# MS5803-2BA.net
KiCad netlist of a schematic drawn in EAGLE
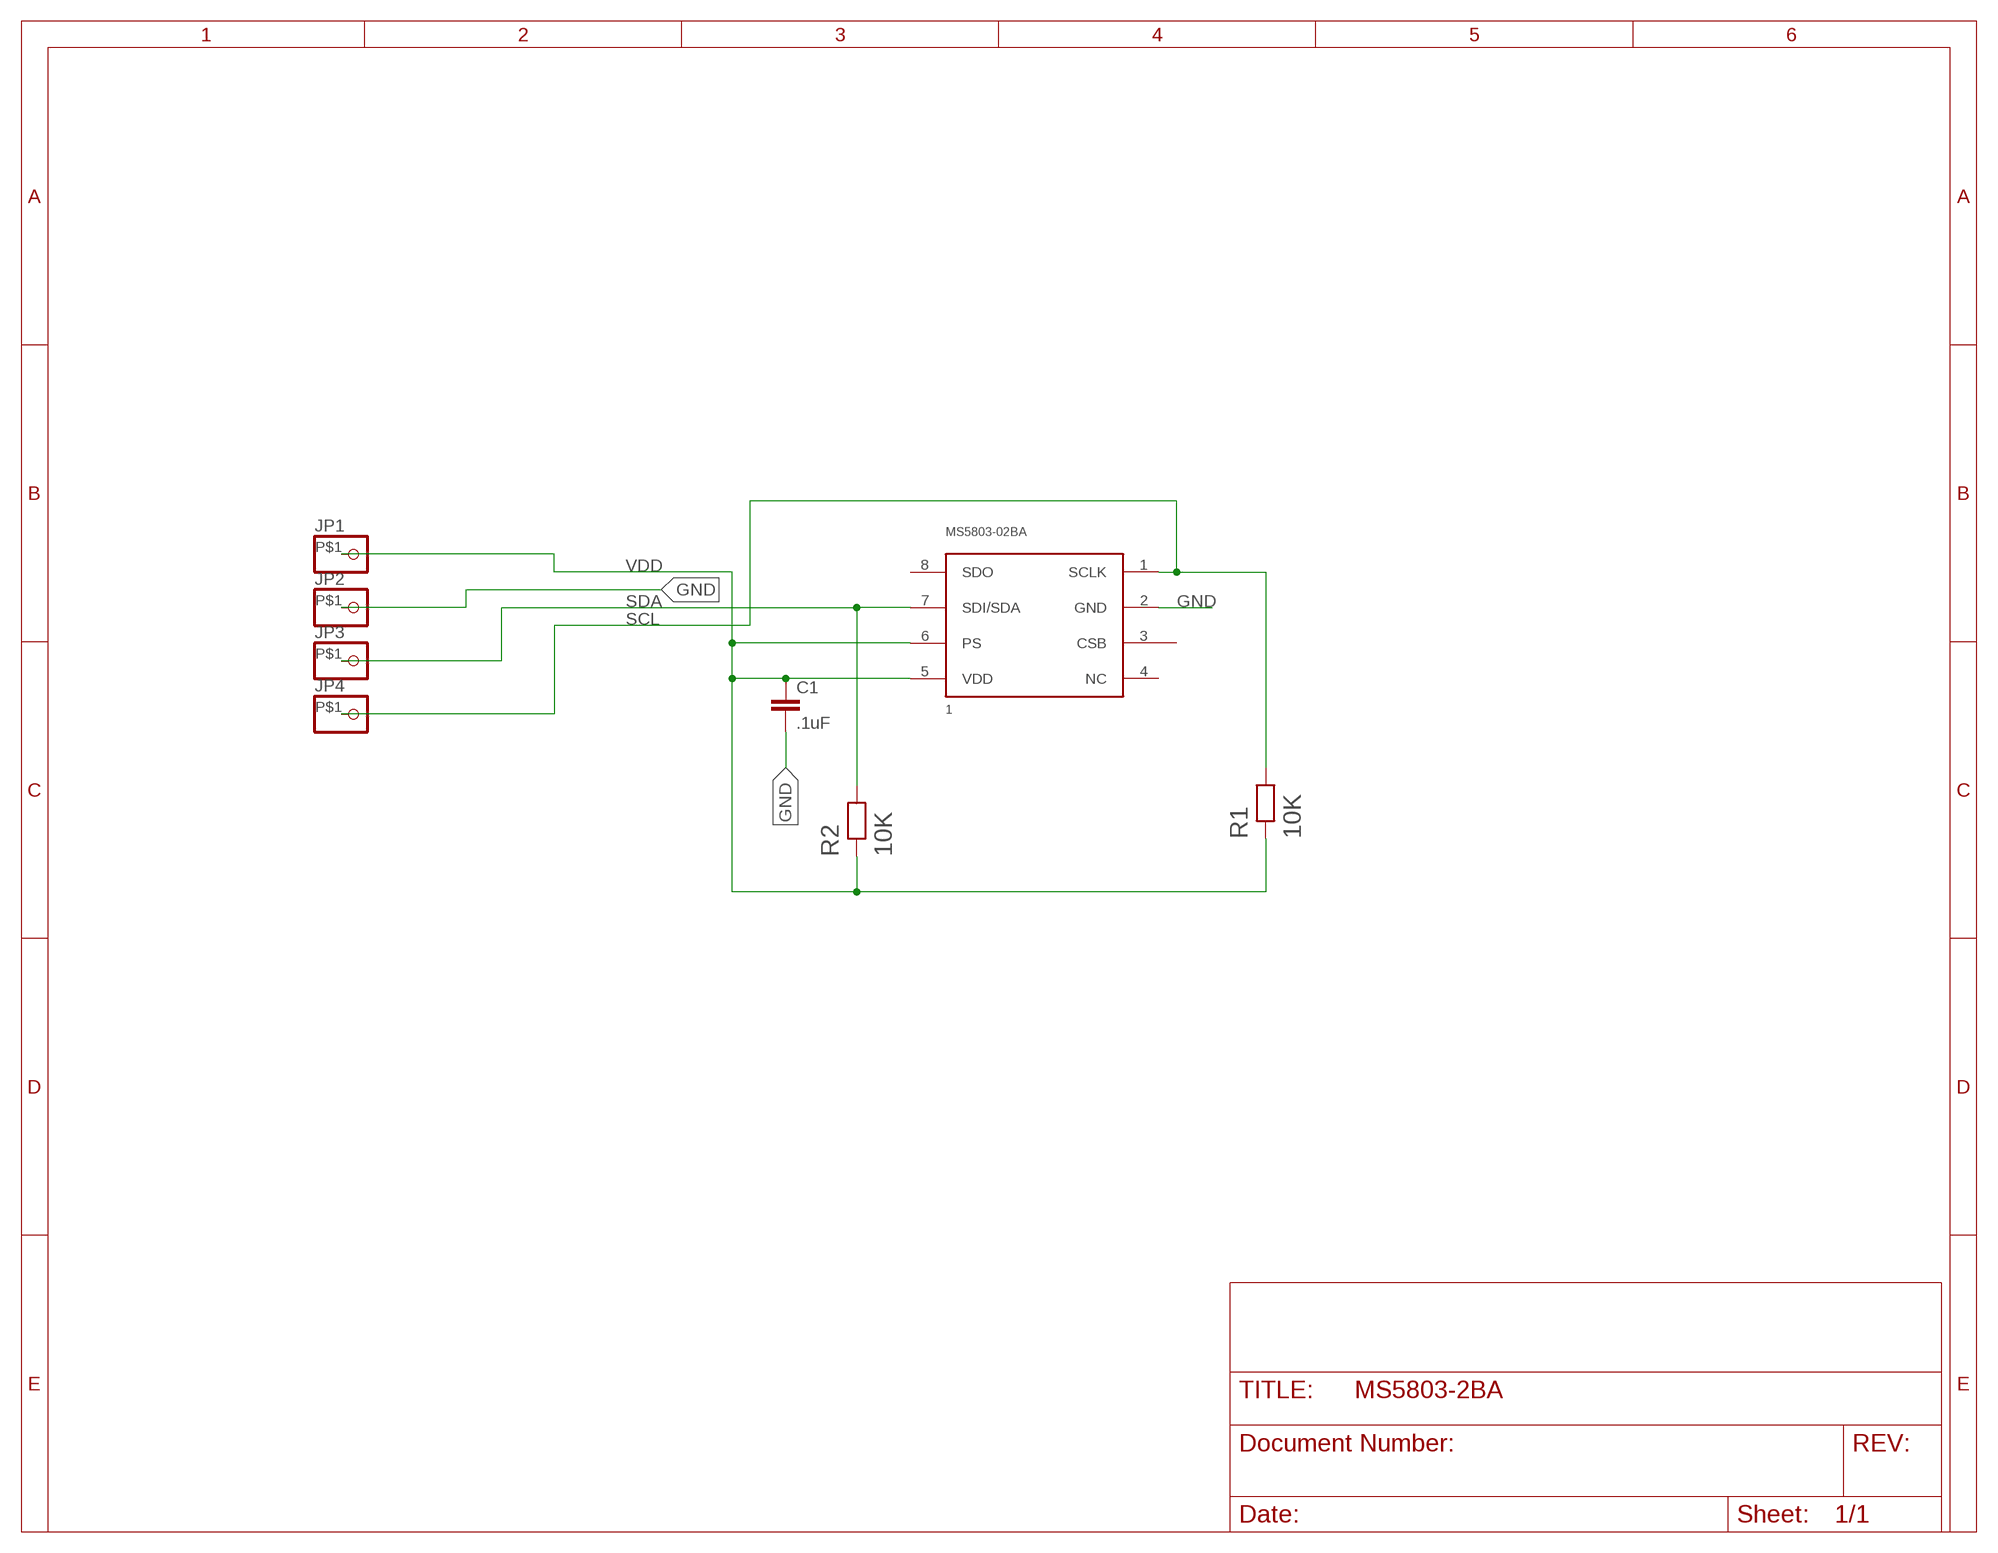
[diagram p0: schematic, sheet 1]

(export (version "E")
  (design (tool "Eeschema 10.0.6"))
  (components
    (comp (ref "C1")
      (value ".1uF")
      (footprint "eagle-import:C0805")
      (libsource (lib "eagle-import") (part "C-EUC0805"))
    )
    (comp (ref "JP1")
      (value "PINHD-1X11X01SM")
      (footprint "eagle-import:1X01SM")
      (libsource (lib "eagle-import") (part "PINHD-1X11X01SM"))
    )
    (comp (ref "JP2")
      (value "PINHD-1X11X01SM")
      (footprint "eagle-import:1X01SM")
      (libsource (lib "eagle-import") (part "PINHD-1X11X01SM"))
    )
    (comp (ref "JP3")
      (value "PINHD-1X11X01SM")
      (footprint "eagle-import:1X01SM")
      (libsource (lib "eagle-import") (part "PINHD-1X11X01SM"))
    )
    (comp (ref "JP4")
      (value "PINHD-1X11X01SM")
      (footprint "eagle-import:1X01SM")
      (libsource (lib "eagle-import") (part "PINHD-1X11X01SM"))
    )
    (comp (ref "MS5803-02BA")
      (value "1")
      (footprint "eagle-import:MS5803-02BA")
      (libsource (lib "eagle-import") (part "MS5803-02BASMD"))
    )
    (comp (ref "R1")
      (value "10K")
      (footprint "eagle-import:2012(0805)RESISTOR")
      (libsource (lib "eagle-import") (part "10KOHM_2012(0805)_SMDSMD"))
    )
    (comp (ref "R2")
      (value "10K")
      (footprint "eagle-import:2012(0805)RESISTOR")
      (libsource (lib "eagle-import") (part "10KOHM_2012(0805)_SMDSMD"))
    )
  )
  (nets
    (net (code "1") (name "/SCL") (class "Default")
      (node (ref "JP4") (pin "P$1") (pinfunction "1_P$1") (pintype "passive"))
      (node (ref "MS5803-02BA") (pin "1") (pinfunction "SCLK_1") (pintype "bidirectional"))
      (node (ref "R1") (pin "2") (pinfunction "2_2") (pintype "passive"))
    )
    (net (code "2") (name "/SDA") (class "Default")
      (node (ref "JP3") (pin "P$1") (pinfunction "1_P$1") (pintype "passive"))
      (node (ref "MS5803-02BA") (pin "7") (pinfunction "SDI/SDA_7") (pintype "bidirectional"))
      (node (ref "R2") (pin "2") (pinfunction "2_2") (pintype "passive"))
    )
    (net (code "3") (name "/VDD") (class "Default")
      (node (ref "C1") (pin "1") (pinfunction "1_1") (pintype "passive"))
      (node (ref "JP1") (pin "P$1") (pinfunction "1_P$1") (pintype "passive"))
      (node (ref "MS5803-02BA") (pin "5") (pinfunction "VDD_5") (pintype "power_in"))
      (node (ref "MS5803-02BA") (pin "6") (pinfunction "PS_6") (pintype "bidirectional"))
      (node (ref "R1") (pin "1") (pinfunction "1_1") (pintype "passive"))
      (node (ref "R2") (pin "1") (pinfunction "1_1") (pintype "passive"))
    )
    (net (code "4") (name "GND") (class "Default")
      (node (ref "C1") (pin "2") (pinfunction "2_2") (pintype "passive"))
      (node (ref "JP2") (pin "P$1") (pinfunction "1_P$1") (pintype "passive"))
      (node (ref "MS5803-02BA") (pin "2") (pinfunction "GND_2") (pintype "bidirectional"))
    )
    (net (code "5") (name "unconnected-(MS5803-02BA-CSB-Pad3)") (class "Default")
      (node (ref "MS5803-02BA") (pin "3") (pinfunction "CSB_3") (pintype "bidirectional"))
    )
    (net (code "6") (name "unconnected-(MS5803-02BA-NC-Pad4)") (class "Default")
      (node (ref "MS5803-02BA") (pin "4") (pinfunction "NC_4") (pintype "no_connect"))
    )
    (net (code "7") (name "unconnected-(MS5803-02BA-SDO-Pad8)") (class "Default")
      (node (ref "MS5803-02BA") (pin "8") (pinfunction "SDO_8") (pintype "bidirectional"))
    )
  )
)
